# Tinybot_v1.net
KiCad netlist of a schematic drawn in EAGLE
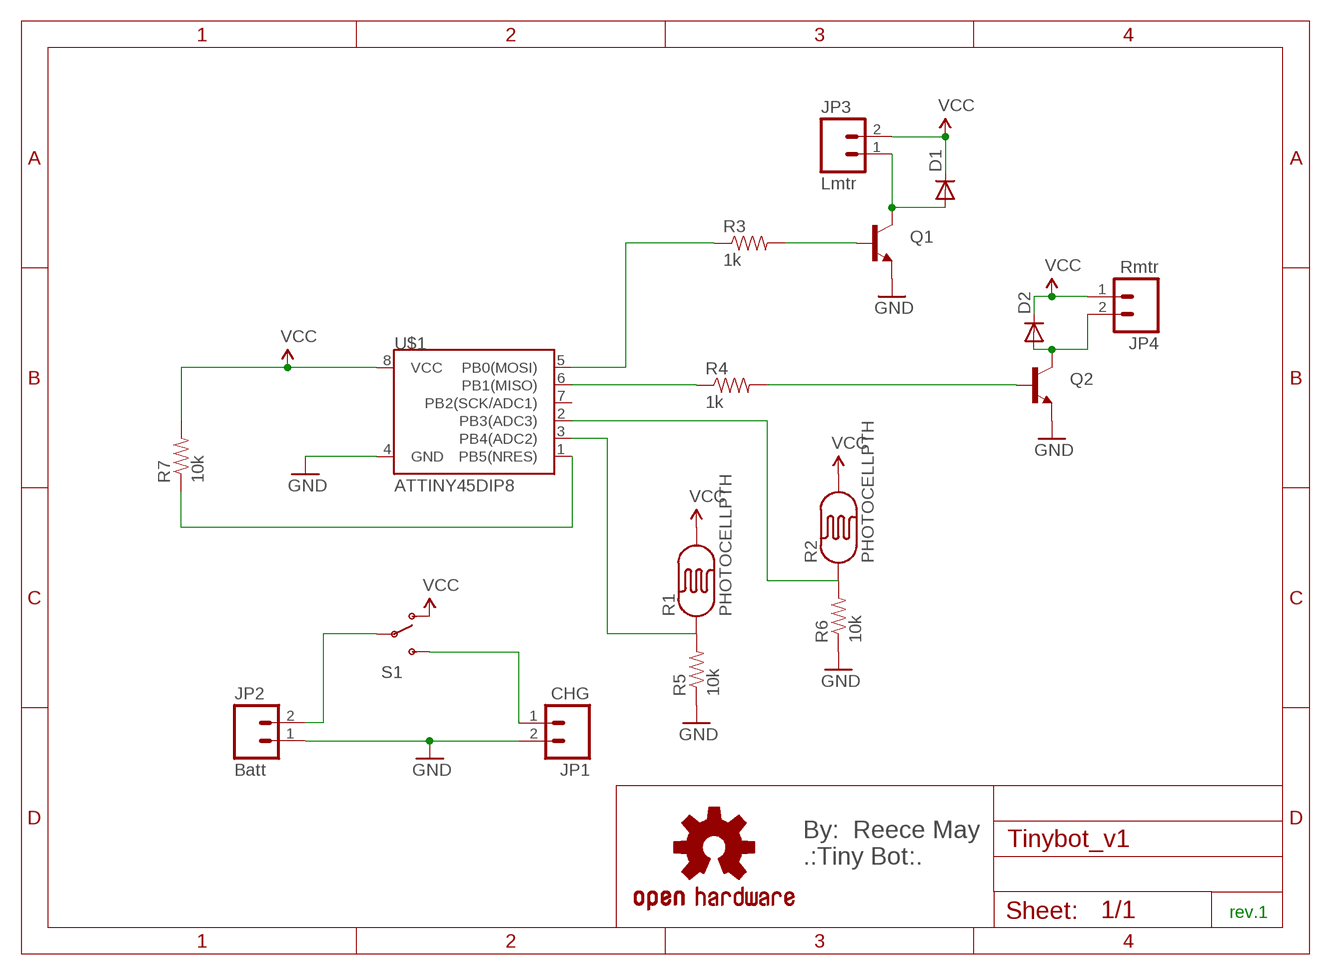
[diagram p0: schematic, sheet 1]

(export (version "E")
  (design (tool "Eeschema 10.0.6"))
  (components
    (comp (ref "D1")
      (value "DIODESOD")
      (footprint "eagle-import:SOD-323")
      (libsource (lib "eagle-import") (part "DIODESOD"))
    )
    (comp (ref "D2")
      (value "DIODESOD")
      (footprint "eagle-import:SOD-323")
      (libsource (lib "eagle-import") (part "DIODESOD"))
    )
    (comp (ref "JP1")
      (value "CHG")
      (footprint "eagle-import:1X02")
      (libsource (lib "eagle-import") (part "M02PTH"))
    )
    (comp (ref "JP2")
      (value "Batt")
      (footprint "eagle-import:1X02")
      (libsource (lib "eagle-import") (part "M02PTH"))
    )
    (comp (ref "JP3")
      (value "Lmtr")
      (footprint "eagle-import:1X02")
      (libsource (lib "eagle-import") (part "M02PTH"))
    )
    (comp (ref "JP4")
      (value "Rmtr")
      (footprint "eagle-import:1X02")
      (libsource (lib "eagle-import") (part "M02PTH"))
    )
    (comp (ref "Q1")
      (value "TRANSISTOR_NPNSOT23")
      (footprint "eagle-import:SOT23")
      (libsource (lib "eagle-import") (part "TRANSISTOR_NPNSOT23"))
    )
    (comp (ref "Q2")
      (value "TRANSISTOR_NPNSOT23")
      (footprint "eagle-import:SOT23")
      (libsource (lib "eagle-import") (part "TRANSISTOR_NPNSOT23"))
    )
    (comp (ref "R1")
      (value "PHOTOCELLPTH")
      (footprint "eagle-import:PHOTOCELL")
      (libsource (lib "eagle-import") (part "PHOTOCELLPTH"))
    )
    (comp (ref "R2")
      (value "PHOTOCELLPTH")
      (footprint "eagle-import:PHOTOCELL")
      (libsource (lib "eagle-import") (part "PHOTOCELLPTH"))
    )
    (comp (ref "R3")
      (value "1k")
      (footprint "eagle-import:0805")
      (libsource (lib "eagle-import") (part "RESISTOR0805-RES"))
    )
    (comp (ref "R4")
      (value "1k")
      (footprint "eagle-import:0805")
      (libsource (lib "eagle-import") (part "RESISTOR0805-RES"))
    )
    (comp (ref "R5")
      (value "10k")
      (footprint "eagle-import:0805")
      (libsource (lib "eagle-import") (part "RESISTOR0805-RES"))
    )
    (comp (ref "R6")
      (value "10k")
      (footprint "eagle-import:0805")
      (libsource (lib "eagle-import") (part "RESISTOR0805-RES"))
    )
    (comp (ref "R7")
      (value "10k")
      (footprint "eagle-import:0805")
      (libsource (lib "eagle-import") (part "RESISTOR0805-RES"))
    )
    (comp (ref "S1")
      (value "SWITCH-SPST-SMD-A")
      (footprint "eagle-import:SWITCH-SPST-SMD-A")
      (libsource (lib "eagle-import") (part "SWITCH-SPST-SMD-A"))
    )
    (comp (ref "U$1")
      (value "ATTINY45DIP8")
      (footprint "eagle-import:DIP08")
      (libsource (lib "eagle-import") (part "ATTINY45DIP8"))
    )
    (comp (ref "U$2")
      (value "OSHW-LOGOM")
      (footprint "eagle-import:OSHW-LOGO-M")
      (libsource (lib "eagle-import") (part "OSHW-LOGOM"))
    )
  )
  (nets
    (net (code "1") (name "GND") (class "Default")
      (node (ref "JP1") (pin "2") (pinfunction "2_2") (pintype "passive"))
      (node (ref "JP2") (pin "1") (pinfunction "1_1") (pintype "passive"))
      (node (ref "Q1") (pin "2") (pinfunction "E_2") (pintype "passive"))
      (node (ref "Q2") (pin "2") (pinfunction "E_2") (pintype "passive"))
      (node (ref "R5") (pin "1") (pinfunction "1_1") (pintype "passive"))
      (node (ref "R6") (pin "1") (pinfunction "1_1") (pintype "passive"))
      (node (ref "U$1") (pin "4") (pinfunction "GND_4") (pintype "bidirectional"))
    )
    (net (code "2") (name "Net-(D1-A)") (class "Default")
      (node (ref "D1") (pin "2") (pinfunction "A_2") (pintype "passive"))
      (node (ref "JP3") (pin "1") (pinfunction "1_1") (pintype "passive"))
      (node (ref "Q1") (pin "3") (pinfunction "C_3") (pintype "passive"))
    )
    (net (code "3") (name "Net-(D2-A)") (class "Default")
      (node (ref "D2") (pin "2") (pinfunction "A_2") (pintype "passive"))
      (node (ref "JP4") (pin "2") (pinfunction "2_2") (pintype "passive"))
      (node (ref "Q2") (pin "3") (pinfunction "C_3") (pintype "passive"))
    )
    (net (code "4") (name "Net-(Q1-B)") (class "Default")
      (node (ref "Q1") (pin "1") (pinfunction "B_1") (pintype "passive"))
      (node (ref "R3") (pin "2") (pinfunction "2_2") (pintype "passive"))
    )
    (net (code "5") (name "Net-(Q2-B)") (class "Default")
      (node (ref "Q2") (pin "1") (pinfunction "B_1") (pintype "passive"))
      (node (ref "R4") (pin "2") (pinfunction "2_2") (pintype "passive"))
    )
    (net (code "6") (name "Net-(R1-P$1)") (class "Default")
      (node (ref "R1") (pin "1") (pinfunction "P$1_1") (pintype "bidirectional"))
      (node (ref "R5") (pin "2") (pinfunction "2_2") (pintype "passive"))
      (node (ref "U$1") (pin "3") (pinfunction "PB4(ADC2)_3") (pintype "bidirectional"))
    )
    (net (code "7") (name "Net-(R2-P$1)") (class "Default")
      (node (ref "R2") (pin "1") (pinfunction "P$1_1") (pintype "bidirectional"))
      (node (ref "R6") (pin "2") (pinfunction "2_2") (pintype "passive"))
      (node (ref "U$1") (pin "2") (pinfunction "PB3(ADC3)_2") (pintype "bidirectional"))
    )
    (net (code "8") (name "Net-(S1-P)") (class "Default")
      (node (ref "JP2") (pin "2") (pinfunction "2_2") (pintype "passive"))
      (node (ref "S1") (pin "2") (pinfunction "P_2") (pintype "passive"))
    )
    (net (code "9") (name "Net-(S1-S)") (class "Default")
      (node (ref "JP1") (pin "1") (pinfunction "1_1") (pintype "passive"))
      (node (ref "S1") (pin "3") (pinfunction "S_3") (pintype "passive"))
    )
    (net (code "10") (name "Net-(U$1-PB0(MOSI))") (class "Default")
      (node (ref "R3") (pin "1") (pinfunction "1_1") (pintype "passive"))
      (node (ref "U$1") (pin "5") (pinfunction "PB0(MOSI)_5") (pintype "bidirectional"))
    )
    (net (code "11") (name "Net-(U$1-PB1(MISO))") (class "Default")
      (node (ref "R4") (pin "1") (pinfunction "1_1") (pintype "passive"))
      (node (ref "U$1") (pin "6") (pinfunction "PB1(MISO)_6") (pintype "bidirectional"))
    )
    (net (code "12") (name "Net-(U$1-PB5(NRES))") (class "Default")
      (node (ref "R7") (pin "1") (pinfunction "1_1") (pintype "passive"))
      (node (ref "U$1") (pin "1") (pinfunction "PB5(NRES)_1") (pintype "bidirectional"))
    )
    (net (code "13") (name "VCC") (class "Default")
      (node (ref "D1") (pin "1") (pinfunction "C_1") (pintype "passive"))
      (node (ref "D2") (pin "1") (pinfunction "C_1") (pintype "passive"))
      (node (ref "JP3") (pin "2") (pinfunction "2_2") (pintype "passive"))
      (node (ref "JP4") (pin "1") (pinfunction "1_1") (pintype "passive"))
      (node (ref "R1") (pin "2") (pinfunction "P$2_2") (pintype "bidirectional"))
      (node (ref "R2") (pin "2") (pinfunction "P$2_2") (pintype "bidirectional"))
      (node (ref "R7") (pin "2") (pinfunction "2_2") (pintype "passive"))
      (node (ref "S1") (pin "1") (pinfunction "O_1") (pintype "passive"))
      (node (ref "U$1") (pin "8") (pinfunction "VCC_8") (pintype "bidirectional"))
    )
    (net (code "14") (name "unconnected-(U$1-PB2(SCK{slash}ADC1)-Pad7)") (class "Default")
      (node (ref "U$1") (pin "7") (pinfunction "PB2(SCK/ADC1)_7") (pintype "bidirectional"))
    )
  )
)
